# Gain.net
KiCad netlist of a schematic drawn in EAGLE
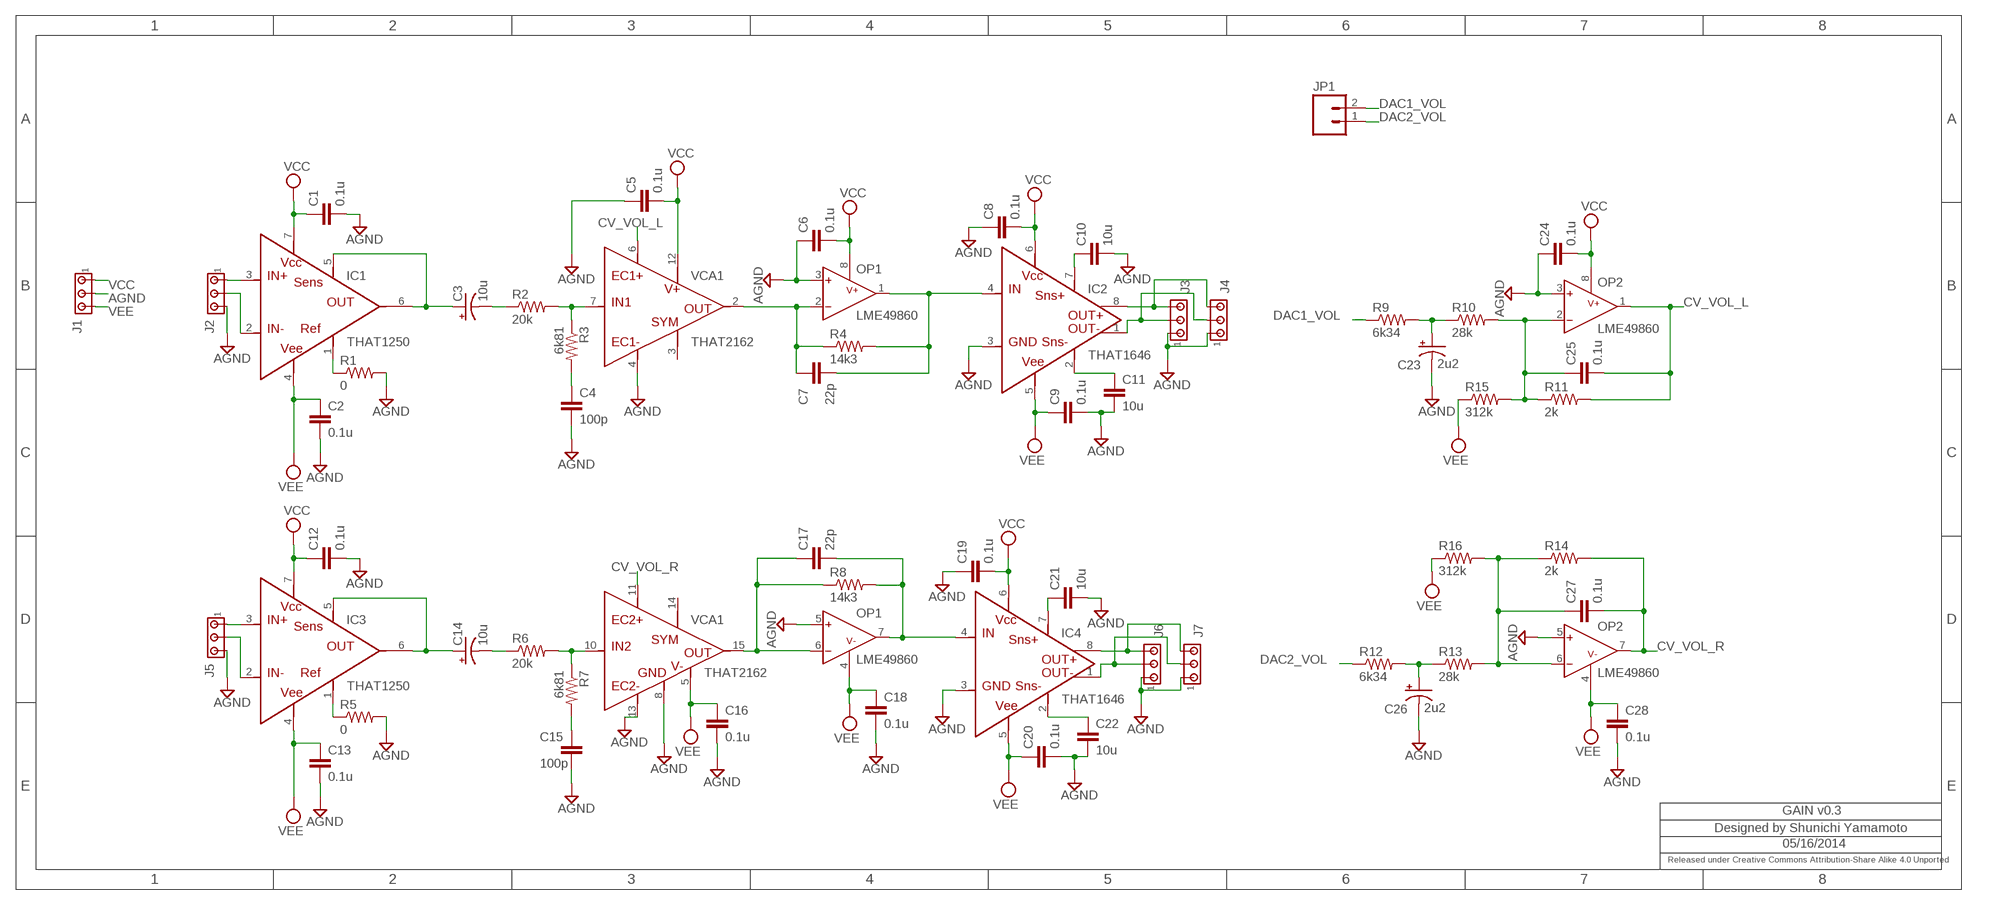
[diagram p0: schematic, sheet 1]

(export (version "E")
  (design (tool "Eeschema 10.0.6"))
  (components
    (comp (ref "C1")
      (value "0.1u")
      (footprint "eagle-import:C2012")
      (libsource (lib "eagle-import") (part "C-EUC2012"))
    )
    (comp (ref "C2")
      (value "0.1u")
      (footprint "eagle-import:C2012")
      (libsource (lib "eagle-import") (part "C-EUC2012"))
    )
    (comp (ref "C3")
      (value "10u")
      (footprint "eagle-import:UD-5X5,8_NICHICON")
      (libsource (lib "eagle-import") (part "CPOL-USUD-5X5,8"))
    )
    (comp (ref "C4")
      (value "100p")
      (footprint "eagle-import:C2012")
      (libsource (lib "eagle-import") (part "C-EUC2012"))
    )
    (comp (ref "C5")
      (value "0.1u")
      (footprint "eagle-import:C2012")
      (libsource (lib "eagle-import") (part "C-EUC2012"))
    )
    (comp (ref "C6")
      (value "0.1u")
      (footprint "eagle-import:C2012")
      (libsource (lib "eagle-import") (part "C-EUC2012"))
    )
    (comp (ref "C7")
      (value "22p")
      (footprint "eagle-import:C2012")
      (libsource (lib "eagle-import") (part "C-EUC2012"))
    )
    (comp (ref "C8")
      (value "0.1u")
      (footprint "eagle-import:C2012")
      (libsource (lib "eagle-import") (part "C-EUC2012"))
    )
    (comp (ref "C9")
      (value "0.1u")
      (footprint "eagle-import:C2012")
      (libsource (lib "eagle-import") (part "C-EUC2012"))
    )
    (comp (ref "C10")
      (value "10u")
      (footprint "eagle-import:C2012")
      (libsource (lib "eagle-import") (part "C-EUC2012"))
    )
    (comp (ref "C11")
      (value "10u")
      (footprint "eagle-import:C2012")
      (libsource (lib "eagle-import") (part "C-EUC2012"))
    )
    (comp (ref "C12")
      (value "0.1u")
      (footprint "eagle-import:C2012")
      (libsource (lib "eagle-import") (part "C-EUC2012"))
    )
    (comp (ref "C13")
      (value "0.1u")
      (footprint "eagle-import:C2012")
      (libsource (lib "eagle-import") (part "C-EUC2012"))
    )
    (comp (ref "C14")
      (value "10u")
      (footprint "eagle-import:UD-5X5,8_NICHICON")
      (libsource (lib "eagle-import") (part "CPOL-USUD-5X5,8"))
    )
    (comp (ref "C15")
      (value "100p")
      (footprint "eagle-import:C2012")
      (libsource (lib "eagle-import") (part "C-EUC2012"))
    )
    (comp (ref "C16")
      (value "0.1u")
      (footprint "eagle-import:C2012")
      (libsource (lib "eagle-import") (part "C-EUC2012"))
    )
    (comp (ref "C17")
      (value "22p")
      (footprint "eagle-import:C2012")
      (libsource (lib "eagle-import") (part "C-EUC2012"))
    )
    (comp (ref "C18")
      (value "0.1u")
      (footprint "eagle-import:C2012")
      (libsource (lib "eagle-import") (part "C-EUC2012"))
    )
    (comp (ref "C19")
      (value "0.1u")
      (footprint "eagle-import:C2012")
      (libsource (lib "eagle-import") (part "C-EUC2012"))
    )
    (comp (ref "C20")
      (value "0.1u")
      (footprint "eagle-import:C2012")
      (libsource (lib "eagle-import") (part "C-EUC2012"))
    )
    (comp (ref "C21")
      (value "10u")
      (footprint "eagle-import:C2012")
      (libsource (lib "eagle-import") (part "C-EUC2012"))
    )
    (comp (ref "C22")
      (value "10u")
      (footprint "eagle-import:C2012")
      (libsource (lib "eagle-import") (part "C-EUC2012"))
    )
    (comp (ref "C23")
      (value "2u2")
      (footprint "eagle-import:UD-5X5,8_NICHICON")
      (libsource (lib "eagle-import") (part "CPOL-USUD-5X5,8"))
    )
    (comp (ref "C24")
      (value "0.1u")
      (footprint "eagle-import:C2012")
      (libsource (lib "eagle-import") (part "C-EUC2012"))
    )
    (comp (ref "C25")
      (value "0.1u")
      (footprint "eagle-import:C2012")
      (libsource (lib "eagle-import") (part "C-EUC2012"))
    )
    (comp (ref "C26")
      (value "2u2")
      (footprint "eagle-import:UD-5X5,8_NICHICON")
      (libsource (lib "eagle-import") (part "CPOL-USUD-5X5,8"))
    )
    (comp (ref "C27")
      (value "0.1u")
      (footprint "eagle-import:C2012")
      (libsource (lib "eagle-import") (part "C-EUC2012"))
    )
    (comp (ref "C28")
      (value "0.1u")
      (footprint "eagle-import:C2012")
      (libsource (lib "eagle-import") (part "C-EUC2012"))
    )
    (comp (ref "IC1")
      (value "THAT1250")
      (footprint "eagle-import:SOIC8")
      (libsource (lib "eagle-import") (part "THAT1250"))
    )
    (comp (ref "IC2")
      (value "THAT1646")
      (footprint "eagle-import:SOIC8")
      (libsource (lib "eagle-import") (part "THAT1646"))
    )
    (comp (ref "IC3")
      (value "THAT1250")
      (footprint "eagle-import:SOIC8")
      (libsource (lib "eagle-import") (part "THAT1250"))
    )
    (comp (ref "IC4")
      (value "THAT1646")
      (footprint "eagle-import:SOIC8")
      (libsource (lib "eagle-import") (part "THAT1646"))
    )
    (comp (ref "J1")
      (value "MTA03-156")
      (footprint "eagle-import:1X3MTA")
      (libsource (lib "eagle-import") (part "MTA03-156"))
    )
    (comp (ref "J2")
      (value "MTA03-100")
      (footprint "eagle-import:10X03MTA")
      (libsource (lib "eagle-import") (part "MTA03-100"))
    )
    (comp (ref "J3")
      (value "MTA03-100")
      (footprint "eagle-import:10X03MTA")
      (libsource (lib "eagle-import") (part "MTA03-100"))
    )
    (comp (ref "J4")
      (value "MTA03-100")
      (footprint "eagle-import:10X03MTA")
      (libsource (lib "eagle-import") (part "MTA03-100"))
    )
    (comp (ref "J5")
      (value "MTA03-100")
      (footprint "eagle-import:10X03MTA")
      (libsource (lib "eagle-import") (part "MTA03-100"))
    )
    (comp (ref "J6")
      (value "MTA03-100")
      (footprint "eagle-import:10X03MTA")
      (libsource (lib "eagle-import") (part "MTA03-100"))
    )
    (comp (ref "J7")
      (value "MTA03-100")
      (footprint "eagle-import:10X03MTA")
      (libsource (lib "eagle-import") (part "MTA03-100"))
    )
    (comp (ref "JP1")
      (value "M02PTH")
      (footprint "eagle-import:1X02")
      (libsource (lib "eagle-import") (part "M02PTH"))
    )
    (comp (ref "OP1")
      (value "LME49860")
      (footprint "eagle-import:SOIC8@1")
      (libsource (lib "eagle-import") (part "LME49860"))
    )
    (comp (ref "OP2")
      (value "LME49860")
      (footprint "eagle-import:SOIC8@1")
      (libsource (lib "eagle-import") (part "LME49860"))
    )
    (comp (ref "R1")
      (value "0")
      (footprint "eagle-import:0805")
      (libsource (lib "eagle-import") (part "RESISTOR0805-RES"))
    )
    (comp (ref "R2")
      (value "20k")
      (footprint "eagle-import:0805")
      (libsource (lib "eagle-import") (part "RESISTOR0805-RES"))
    )
    (comp (ref "R3")
      (value "6k81")
      (footprint "eagle-import:0805")
      (libsource (lib "eagle-import") (part "RESISTOR0805-RES"))
    )
    (comp (ref "R4")
      (value "14k3")
      (footprint "eagle-import:0805")
      (libsource (lib "eagle-import") (part "RESISTOR0805-RES"))
    )
    (comp (ref "R5")
      (value "0")
      (footprint "eagle-import:0805")
      (libsource (lib "eagle-import") (part "RESISTOR0805-RES"))
    )
    (comp (ref "R6")
      (value "20k")
      (footprint "eagle-import:0805")
      (libsource (lib "eagle-import") (part "RESISTOR0805-RES"))
    )
    (comp (ref "R7")
      (value "6k81")
      (footprint "eagle-import:0805")
      (libsource (lib "eagle-import") (part "RESISTOR0805-RES"))
    )
    (comp (ref "R8")
      (value "14k3")
      (footprint "eagle-import:0805")
      (libsource (lib "eagle-import") (part "RESISTOR0805-RES"))
    )
    (comp (ref "R9")
      (value "6k34")
      (footprint "eagle-import:0805")
      (libsource (lib "eagle-import") (part "RESISTOR0805-RES"))
    )
    (comp (ref "R10")
      (value "28k")
      (footprint "eagle-import:0805")
      (libsource (lib "eagle-import") (part "RESISTOR0805-RES"))
    )
    (comp (ref "R11")
      (value "2k")
      (footprint "eagle-import:0805")
      (libsource (lib "eagle-import") (part "RESISTOR0805-RES"))
    )
    (comp (ref "R12")
      (value "6k34")
      (footprint "eagle-import:0805")
      (libsource (lib "eagle-import") (part "RESISTOR0805-RES"))
    )
    (comp (ref "R13")
      (value "28k")
      (footprint "eagle-import:0805")
      (libsource (lib "eagle-import") (part "RESISTOR0805-RES"))
    )
    (comp (ref "R14")
      (value "2k")
      (footprint "eagle-import:0805")
      (libsource (lib "eagle-import") (part "RESISTOR0805-RES"))
    )
    (comp (ref "R15")
      (value "312k")
      (footprint "eagle-import:0805")
      (libsource (lib "eagle-import") (part "RESISTOR0805-RES"))
    )
    (comp (ref "R16")
      (value "312k")
      (footprint "eagle-import:0805")
      (libsource (lib "eagle-import") (part "RESISTOR0805-RES"))
    )
    (comp (ref "VCA1")
      (value "THAT2162")
      (footprint "eagle-import:QSOP-16")
      (libsource (lib "eagle-import") (part "THAT2162"))
    )
  )
  (nets
    (net (code "1") (name "/CV_VOL_L") (class "Default")
      (node (ref "C25") (pin "2") (pinfunction "2_2") (pintype "passive"))
      (node (ref "OP2") (pin "1") (pinfunction "OUTA_1") (pintype "output"))
      (node (ref "R11") (pin "2") (pinfunction "2_2") (pintype "passive"))
      (node (ref "VCA1") (pin "6") (pinfunction "EC1+_6") (pintype "bidirectional"))
    )
    (net (code "2") (name "/CV_VOL_R") (class "Default")
      (node (ref "C27") (pin "2") (pinfunction "2_2") (pintype "passive"))
      (node (ref "OP2") (pin "7") (pinfunction "OUTB_7") (pintype "output"))
      (node (ref "R14") (pin "2") (pinfunction "2_2") (pintype "passive"))
      (node (ref "VCA1") (pin "11") (pinfunction "EC2+_11") (pintype "input"))
    )
    (net (code "3") (name "/DAC1_VOL") (class "Default")
      (node (ref "JP1") (pin "2") (pinfunction "2_2") (pintype "passive"))
      (node (ref "R9") (pin "1") (pinfunction "1_1") (pintype "passive"))
    )
    (net (code "4") (name "/DAC2_VOL") (class "Default")
      (node (ref "JP1") (pin "1") (pinfunction "1_1") (pintype "passive"))
      (node (ref "R12") (pin "1") (pinfunction "1_1") (pintype "passive"))
    )
    (net (code "5") (name "AGND") (class "Default")
      (node (ref "C1") (pin "2") (pinfunction "2_2") (pintype "passive"))
      (node (ref "C10") (pin "2") (pinfunction "2_2") (pintype "passive"))
      (node (ref "C11") (pin "2") (pinfunction "2_2") (pintype "passive"))
      (node (ref "C12") (pin "2") (pinfunction "2_2") (pintype "passive"))
      (node (ref "C13") (pin "2") (pinfunction "2_2") (pintype "passive"))
      (node (ref "C15") (pin "2") (pinfunction "2_2") (pintype "passive"))
      (node (ref "C16") (pin "2") (pinfunction "2_2") (pintype "passive"))
      (node (ref "C18") (pin "2") (pinfunction "2_2") (pintype "passive"))
      (node (ref "C19") (pin "1") (pinfunction "1_1") (pintype "passive"))
      (node (ref "C2") (pin "2") (pinfunction "2_2") (pintype "passive"))
      (node (ref "C20") (pin "2") (pinfunction "2_2") (pintype "passive"))
      (node (ref "C21") (pin "2") (pinfunction "2_2") (pintype "passive"))
      (node (ref "C22") (pin "2") (pinfunction "2_2") (pintype "passive"))
      (node (ref "C23") (pin "-") (pinfunction "-_-") (pintype "passive"))
      (node (ref "C24") (pin "1") (pinfunction "1_1") (pintype "passive"))
      (node (ref "C26") (pin "-") (pinfunction "-_-") (pintype "passive"))
      (node (ref "C28") (pin "2") (pinfunction "2_2") (pintype "passive"))
      (node (ref "C4") (pin "2") (pinfunction "2_2") (pintype "passive"))
      (node (ref "C5") (pin "1") (pinfunction "1_1") (pintype "passive"))
      (node (ref "C6") (pin "1") (pinfunction "1_1") (pintype "passive"))
      (node (ref "C8") (pin "1") (pinfunction "1_1") (pintype "passive"))
      (node (ref "C9") (pin "2") (pinfunction "2_2") (pintype "passive"))
      (node (ref "IC2") (pin "3") (pinfunction "GND_3") (pintype "input"))
      (node (ref "IC4") (pin "3") (pinfunction "GND_3") (pintype "input"))
      (node (ref "J1") (pin "2") (pinfunction "2_2") (pintype "passive"))
      (node (ref "J2") (pin "3") (pinfunction "3_3") (pintype "passive"))
      (node (ref "J3") (pin "1") (pinfunction "1_1") (pintype "passive"))
      (node (ref "J4") (pin "1") (pinfunction "1_1") (pintype "passive"))
      (node (ref "J5") (pin "3") (pinfunction "3_3") (pintype "passive"))
      (node (ref "J6") (pin "1") (pinfunction "1_1") (pintype "passive"))
      (node (ref "J7") (pin "1") (pinfunction "1_1") (pintype "passive"))
      (node (ref "OP1") (pin "3") (pinfunction "INA+_3") (pintype "input"))
      (node (ref "OP1") (pin "5") (pinfunction "INB+_5") (pintype "input"))
      (node (ref "OP2") (pin "3") (pinfunction "INA+_3") (pintype "input"))
      (node (ref "OP2") (pin "5") (pinfunction "INB+_5") (pintype "input"))
      (node (ref "R1") (pin "2") (pinfunction "2_2") (pintype "passive"))
      (node (ref "R5") (pin "2") (pinfunction "2_2") (pintype "passive"))
      (node (ref "VCA1") (pin "13") (pinfunction "EC2-_13") (pintype "power_in"))
      (node (ref "VCA1") (pin "4") (pinfunction "EC1-_4") (pintype "input"))
      (node (ref "VCA1") (pin "8") (pinfunction "GND_8") (pintype "input"))
    )
    (net (code "6") (name "Net-(C3-Pad-)") (class "Default")
      (node (ref "C3") (pin "-") (pinfunction "-_-") (pintype "passive"))
      (node (ref "R2") (pin "1") (pinfunction "1_1") (pintype "passive"))
    )
    (net (code "7") (name "Net-(C4-Pad1)") (class "Default")
      (node (ref "C4") (pin "1") (pinfunction "1_1") (pintype "passive"))
      (node (ref "R3") (pin "2") (pinfunction "2_2") (pintype "passive"))
    )
    (net (code "8") (name "Net-(C14-Pad-)") (class "Default")
      (node (ref "C14") (pin "-") (pinfunction "-_-") (pintype "passive"))
      (node (ref "R6") (pin "1") (pinfunction "1_1") (pintype "passive"))
    )
    (net (code "9") (name "Net-(C15-Pad1)") (class "Default")
      (node (ref "C15") (pin "1") (pinfunction "1_1") (pintype "passive"))
      (node (ref "R7") (pin "2") (pinfunction "2_2") (pintype "passive"))
    )
    (net (code "10") (name "Net-(C23-Pad+)") (class "Default")
      (node (ref "C23") (pin "+") (pinfunction "+_+") (pintype "passive"))
      (node (ref "R10") (pin "1") (pinfunction "1_1") (pintype "passive"))
      (node (ref "R9") (pin "2") (pinfunction "2_2") (pintype "passive"))
    )
    (net (code "11") (name "Net-(C26-Pad+)") (class "Default")
      (node (ref "C26") (pin "+") (pinfunction "+_+") (pintype "passive"))
      (node (ref "R12") (pin "2") (pinfunction "2_2") (pintype "passive"))
      (node (ref "R13") (pin "1") (pinfunction "1_1") (pintype "passive"))
    )
    (net (code "12") (name "Net-(IC1-IN+)") (class "Default")
      (node (ref "IC1") (pin "3") (pinfunction "IN+_3") (pintype "input"))
      (node (ref "J2") (pin "1") (pinfunction "1_1") (pintype "passive"))
    )
    (net (code "13") (name "Net-(IC1-IN-)") (class "Default")
      (node (ref "IC1") (pin "2") (pinfunction "IN-_2") (pintype "input"))
      (node (ref "J2") (pin "2") (pinfunction "2_2") (pintype "passive"))
    )
    (net (code "14") (name "Net-(IC1-OUT)") (class "Default")
      (node (ref "C3") (pin "+") (pinfunction "+_+") (pintype "passive"))
      (node (ref "IC1") (pin "5") (pinfunction "SENS_5") (pintype "power_in"))
      (node (ref "IC1") (pin "6") (pinfunction "OUT_6") (pintype "output"))
    )
    (net (code "15") (name "Net-(IC1-REF)") (class "Default")
      (node (ref "IC1") (pin "1") (pinfunction "REF_1") (pintype "input"))
      (node (ref "R1") (pin "1") (pinfunction "1_1") (pintype "passive"))
    )
    (net (code "16") (name "Net-(IC2-IN)") (class "Default")
      (node (ref "C7") (pin "2") (pinfunction "2_2") (pintype "passive"))
      (node (ref "IC2") (pin "4") (pinfunction "IN_4") (pintype "input"))
      (node (ref "OP1") (pin "1") (pinfunction "OUTA_1") (pintype "output"))
      (node (ref "R4") (pin "2") (pinfunction "2_2") (pintype "passive"))
    )
    (net (code "17") (name "Net-(IC2-OUT+)") (class "Default")
      (node (ref "IC2") (pin "8") (pinfunction "OUT+_8") (pintype "output"))
      (node (ref "J3") (pin "3") (pinfunction "3_3") (pintype "passive"))
      (node (ref "J4") (pin "3") (pinfunction "3_3") (pintype "passive"))
    )
    (net (code "18") (name "Net-(IC2-OUT-)") (class "Default")
      (node (ref "IC2") (pin "1") (pinfunction "OUT-_1") (pintype "output"))
      (node (ref "J3") (pin "2") (pinfunction "2_2") (pintype "passive"))
      (node (ref "J4") (pin "2") (pinfunction "2_2") (pintype "passive"))
    )
    (net (code "19") (name "Net-(IC2-SNS+)") (class "Default")
      (node (ref "C10") (pin "1") (pinfunction "1_1") (pintype "passive"))
      (node (ref "IC2") (pin "7") (pinfunction "SNS+_7") (pintype "power_in"))
    )
    (net (code "20") (name "Net-(IC2-SNS-)") (class "Default")
      (node (ref "C11") (pin "1") (pinfunction "1_1") (pintype "passive"))
      (node (ref "IC2") (pin "2") (pinfunction "SNS-_2") (pintype "input"))
    )
    (net (code "21") (name "Net-(IC3-IN+)") (class "Default")
      (node (ref "IC3") (pin "3") (pinfunction "IN+_3") (pintype "input"))
      (node (ref "J5") (pin "1") (pinfunction "1_1") (pintype "passive"))
    )
    (net (code "22") (name "Net-(IC3-IN-)") (class "Default")
      (node (ref "IC3") (pin "2") (pinfunction "IN-_2") (pintype "input"))
      (node (ref "J5") (pin "2") (pinfunction "2_2") (pintype "passive"))
    )
    (net (code "23") (name "Net-(IC3-OUT)") (class "Default")
      (node (ref "C14") (pin "+") (pinfunction "+_+") (pintype "passive"))
      (node (ref "IC3") (pin "5") (pinfunction "SENS_5") (pintype "power_in"))
      (node (ref "IC3") (pin "6") (pinfunction "OUT_6") (pintype "output"))
    )
    (net (code "24") (name "Net-(IC3-REF)") (class "Default")
      (node (ref "IC3") (pin "1") (pinfunction "REF_1") (pintype "input"))
      (node (ref "R5") (pin "1") (pinfunction "1_1") (pintype "passive"))
    )
    (net (code "25") (name "Net-(IC4-IN)") (class "Default")
      (node (ref "C17") (pin "2") (pinfunction "2_2") (pintype "passive"))
      (node (ref "IC4") (pin "4") (pinfunction "IN_4") (pintype "input"))
      (node (ref "OP1") (pin "7") (pinfunction "OUTB_7") (pintype "output"))
      (node (ref "R8") (pin "2") (pinfunction "2_2") (pintype "passive"))
    )
    (net (code "26") (name "Net-(IC4-OUT+)") (class "Default")
      (node (ref "IC4") (pin "8") (pinfunction "OUT+_8") (pintype "output"))
      (node (ref "J6") (pin "3") (pinfunction "3_3") (pintype "passive"))
      (node (ref "J7") (pin "3") (pinfunction "3_3") (pintype "passive"))
    )
    (net (code "27") (name "Net-(IC4-OUT-)") (class "Default")
      (node (ref "IC4") (pin "1") (pinfunction "OUT-_1") (pintype "output"))
      (node (ref "J6") (pin "2") (pinfunction "2_2") (pintype "passive"))
      (node (ref "J7") (pin "2") (pinfunction "2_2") (pintype "passive"))
    )
    (net (code "28") (name "Net-(IC4-SNS+)") (class "Default")
      (node (ref "C21") (pin "1") (pinfunction "1_1") (pintype "passive"))
      (node (ref "IC4") (pin "7") (pinfunction "SNS+_7") (pintype "power_in"))
    )
    (net (code "29") (name "Net-(IC4-SNS-)") (class "Default")
      (node (ref "C22") (pin "1") (pinfunction "1_1") (pintype "passive"))
      (node (ref "IC4") (pin "2") (pinfunction "SNS-_2") (pintype "input"))
    )
    (net (code "30") (name "Net-(OP1A-INA-)") (class "Default")
      (node (ref "C7") (pin "1") (pinfunction "1_1") (pintype "passive"))
      (node (ref "OP1") (pin "2") (pinfunction "INA-_2") (pintype "input"))
      (node (ref "R4") (pin "1") (pinfunction "1_1") (pintype "passive"))
      (node (ref "VCA1") (pin "2") (pinfunction "OUT1_2") (pintype "output"))
    )
    (net (code "31") (name "Net-(OP1B-INB-)") (class "Default")
      (node (ref "C17") (pin "1") (pinfunction "1_1") (pintype "passive"))
      (node (ref "OP1") (pin "6") (pinfunction "INB-_6") (pintype "input"))
      (node (ref "R8") (pin "1") (pinfunction "1_1") (pintype "passive"))
      (node (ref "VCA1") (pin "15") (pinfunction "OUT2_15") (pintype "output"))
    )
    (net (code "32") (name "Net-(OP2A-INA-)") (class "Default")
      (node (ref "C25") (pin "1") (pinfunction "1_1") (pintype "passive"))
      (node (ref "OP2") (pin "2") (pinfunction "INA-_2") (pintype "input"))
      (node (ref "R10") (pin "2") (pinfunction "2_2") (pintype "passive"))
      (node (ref "R11") (pin "1") (pinfunction "1_1") (pintype "passive"))
      (node (ref "R15") (pin "2") (pinfunction "2_2") (pintype "passive"))
    )
    (net (code "33") (name "Net-(OP2B-INB-)") (class "Default")
      (node (ref "C27") (pin "1") (pinfunction "1_1") (pintype "passive"))
      (node (ref "OP2") (pin "6") (pinfunction "INB-_6") (pintype "input"))
      (node (ref "R13") (pin "2") (pinfunction "2_2") (pintype "passive"))
      (node (ref "R14") (pin "1") (pinfunction "1_1") (pintype "passive"))
      (node (ref "R16") (pin "2") (pinfunction "2_2") (pintype "passive"))
    )
    (net (code "34") (name "Net-(VCA1A-IN1)") (class "Default")
      (node (ref "R2") (pin "2") (pinfunction "2_2") (pintype "passive"))
      (node (ref "R3") (pin "1") (pinfunction "1_1") (pintype "passive"))
      (node (ref "VCA1") (pin "7") (pinfunction "IN1_7") (pintype "input"))
    )
    (net (code "35") (name "Net-(VCA1B-IN2)") (class "Default")
      (node (ref "R6") (pin "2") (pinfunction "2_2") (pintype "passive"))
      (node (ref "R7") (pin "1") (pinfunction "1_1") (pintype "passive"))
      (node (ref "VCA1") (pin "10") (pinfunction "IN2_10") (pintype "input"))
    )
    (net (code "36") (name "VCC") (class "Default")
      (node (ref "C1") (pin "1") (pinfunction "1_1") (pintype "passive"))
      (node (ref "C12") (pin "1") (pinfunction "1_1") (pintype "passive"))
      (node (ref "C19") (pin "2") (pinfunction "2_2") (pintype "passive"))
      (node (ref "C24") (pin "2") (pinfunction "2_2") (pintype "passive"))
      (node (ref "C5") (pin "2") (pinfunction "2_2") (pintype "passive"))
      (node (ref "C6") (pin "2") (pinfunction "2_2") (pintype "passive"))
      (node (ref "C8") (pin "2") (pinfunction "2_2") (pintype "passive"))
      (node (ref "IC1") (pin "7") (pinfunction "VCC_7") (pintype "power_in"))
      (node (ref "IC2") (pin "6") (pinfunction "VCC_6") (pintype "bidirectional"))
      (node (ref "IC3") (pin "7") (pinfunction "VCC_7") (pintype "power_in"))
      (node (ref "IC4") (pin "6") (pinfunction "VCC_6") (pintype "bidirectional"))
      (node (ref "J1") (pin "1") (pinfunction "1_1") (pintype "passive"))
      (node (ref "OP1") (pin "8") (pinfunction "V+_8") (pintype "power_in"))
      (node (ref "OP2") (pin "8") (pinfunction "V+_8") (pintype "power_in"))
      (node (ref "VCA1") (pin "12") (pinfunction "V+_12") (pintype "power_in"))
    )
    (net (code "37") (name "VEE") (class "Default")
      (node (ref "C13") (pin "1") (pinfunction "1_1") (pintype "passive"))
      (node (ref "C16") (pin "1") (pinfunction "1_1") (pintype "passive"))
      (node (ref "C18") (pin "1") (pinfunction "1_1") (pintype "passive"))
      (node (ref "C2") (pin "1") (pinfunction "1_1") (pintype "passive"))
      (node (ref "C20") (pin "1") (pinfunction "1_1") (pintype "passive"))
      (node (ref "C28") (pin "1") (pinfunction "1_1") (pintype "passive"))
      (node (ref "C9") (pin "1") (pinfunction "1_1") (pintype "passive"))
      (node (ref "IC1") (pin "4") (pinfunction "VEE_4") (pintype "power_in"))
      (node (ref "IC2") (pin "5") (pinfunction "VEE_5") (pintype "input"))
      (node (ref "IC3") (pin "4") (pinfunction "VEE_4") (pintype "power_in"))
      (node (ref "IC4") (pin "5") (pinfunction "VEE_5") (pintype "input"))
      (node (ref "J1") (pin "3") (pinfunction "3_3") (pintype "passive"))
      (node (ref "OP1") (pin "4") (pinfunction "V-_4") (pintype "power_in"))
      (node (ref "OP2") (pin "4") (pinfunction "V-_4") (pintype "power_in"))
      (node (ref "R15") (pin "1") (pinfunction "1_1") (pintype "passive"))
      (node (ref "R16") (pin "1") (pinfunction "1_1") (pintype "passive"))
      (node (ref "VCA1") (pin "5") (pinfunction "V-_5") (pintype "input"))
    )
    (net (code "38") (name "unconnected-(VCA1A-SYM1-Pad3)") (class "Default")
      (node (ref "VCA1") (pin "3") (pinfunction "SYM1_3") (pintype "input"))
    )
    (net (code "39") (name "unconnected-(VCA1B-SYM2-Pad14)") (class "Default")
      (node (ref "VCA1") (pin "14") (pinfunction "SYM2_14") (pintype "input"))
    )
  )
)
